# EEPROM.net
KiCad netlist of a schematic drawn in Altium Designer
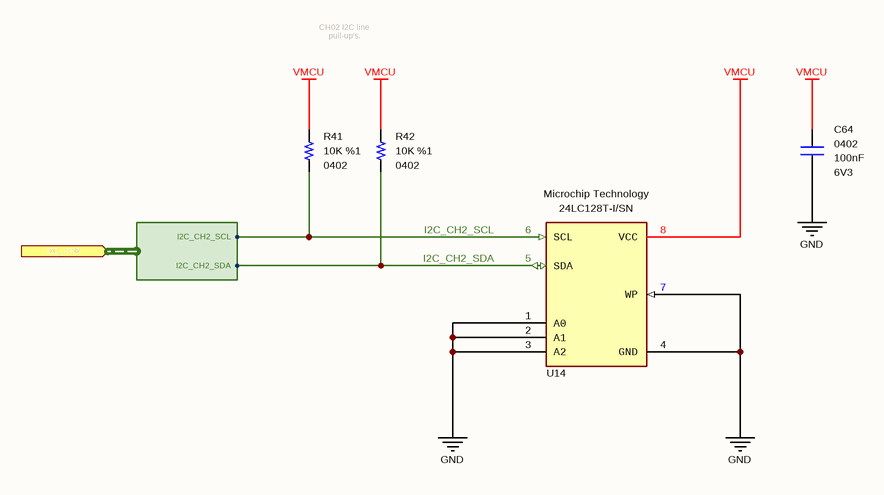
[diagram p0: EEPROM.SchDoc]

(export (version "E")
  (design (tool "Eeschema 10.0.6"))
  (components
    (comp (ref "C64")
      (value "100nF")
      (footprint "CAPACITOR_0402")
      (description "Capacitor - 100nF [0402-6V3] (Ceramic)")
      (fields
        (field (name "TOLERANCE") "%10")
        (field (name "CASE") "0402")
        (field (name "VOLTAGE") "6V3")
        (field (name "MANUFACTURER PART NUMBER") "04026D104KAT4A")
      )
      (libsource (lib "Ovoo_Library") (part "Capacitor - 100nF [0402-6V3]"))
    )
    (comp (ref "R41")
      (value "10K")
      (footprint "RESISTOR_0402")
      (description "Thick Film Resistors - SMD 1/16 W 10 Kohms 1%")
      (fields
        (field (name "TOLERANCE") "%1")
        (field (name "CASE") "0402")
        (field (name "MANUFACTURER PART NUMBER") "CRCW040210K0FKED")
        (field (name "MOUSER PART NUMBER") "71-CRCW0402-10K-E3")
      )
      (libsource (lib "Ovoo_Library") (part "Resistor - 10K"))
    )
    (comp (ref "R42")
      (value "10K")
      (footprint "RESISTOR_0402")
      (description "Thick Film Resistors - SMD 1/16 W 10 Kohms 1%")
      (fields
        (field (name "TOLERANCE") "%1")
        (field (name "CASE") "0402")
        (field (name "MANUFACTURER PART NUMBER") "CRCW040210K0FKED")
        (field (name "MOUSER PART NUMBER") "71-CRCW0402-10K-E3")
      )
      (libsource (lib "Ovoo_Library") (part "Resistor - 10K"))
    )
    (comp (ref "U14")
      (value "EEPROM")
      (footprint "SOIC-8")
      (fields
        (field (name "MANUFACTURER PART NUMBER") "24LC128T-I/SN")
        (field (name "MANUFACTURER NAME") "Microchip Technology")
        (field (name "MOUSER PART NUMBER") "579-24LC128T-I/SN")
      )
      (libsource (lib "Ovoo_Library") (part "IC - 24LC128"))
    )
  )
  (nets
    (net (code "2") (name "/I2C_CH2_SCL") (class "Default")
      (node (ref "R41") (pin "1") (pinfunction "1_1") (pintype "passive"))
      (node (ref "U14") (pin "6") (pinfunction "SCL_6") (pintype "input"))
    )
    (net (code "3") (name "/I2C_CH2_SDA") (class "Default")
      (node (ref "R42") (pin "1") (pinfunction "1_1") (pintype "passive"))
      (node (ref "U14") (pin "5") (pinfunction "SDA_5") (pintype "bidirectional"))
    )
    (net (code "5") (name "GND") (class "Default")
      (node (ref "C64") (pin "1") (pinfunction "1_1") (pintype "passive"))
      (node (ref "U14") (pin "1") (pinfunction "A0_1") (pintype "passive"))
      (node (ref "U14") (pin "2") (pinfunction "A1_2") (pintype "passive"))
      (node (ref "U14") (pin "3") (pinfunction "A2_3") (pintype "passive"))
      (node (ref "U14") (pin "4") (pinfunction "GND_4") (pintype "passive"))
      (node (ref "U14") (pin "7") (pinfunction "WP_7") (pintype "input"))
    )
    (net (code "6") (name "VMCU") (class "Default")
      (node (ref "C64") (pin "2") (pinfunction "2_2") (pintype "passive"))
      (node (ref "R41") (pin "2") (pinfunction "2_2") (pintype "passive"))
      (node (ref "R42") (pin "2") (pinfunction "2_2") (pintype "passive"))
      (node (ref "U14") (pin "8") (pinfunction "VCC_8") (pintype "power_in"))
    )
  )
)
